# ZX_UNO_Aplus_HAT2.net
KiCad netlist of a schematic drawn in Altium Designer
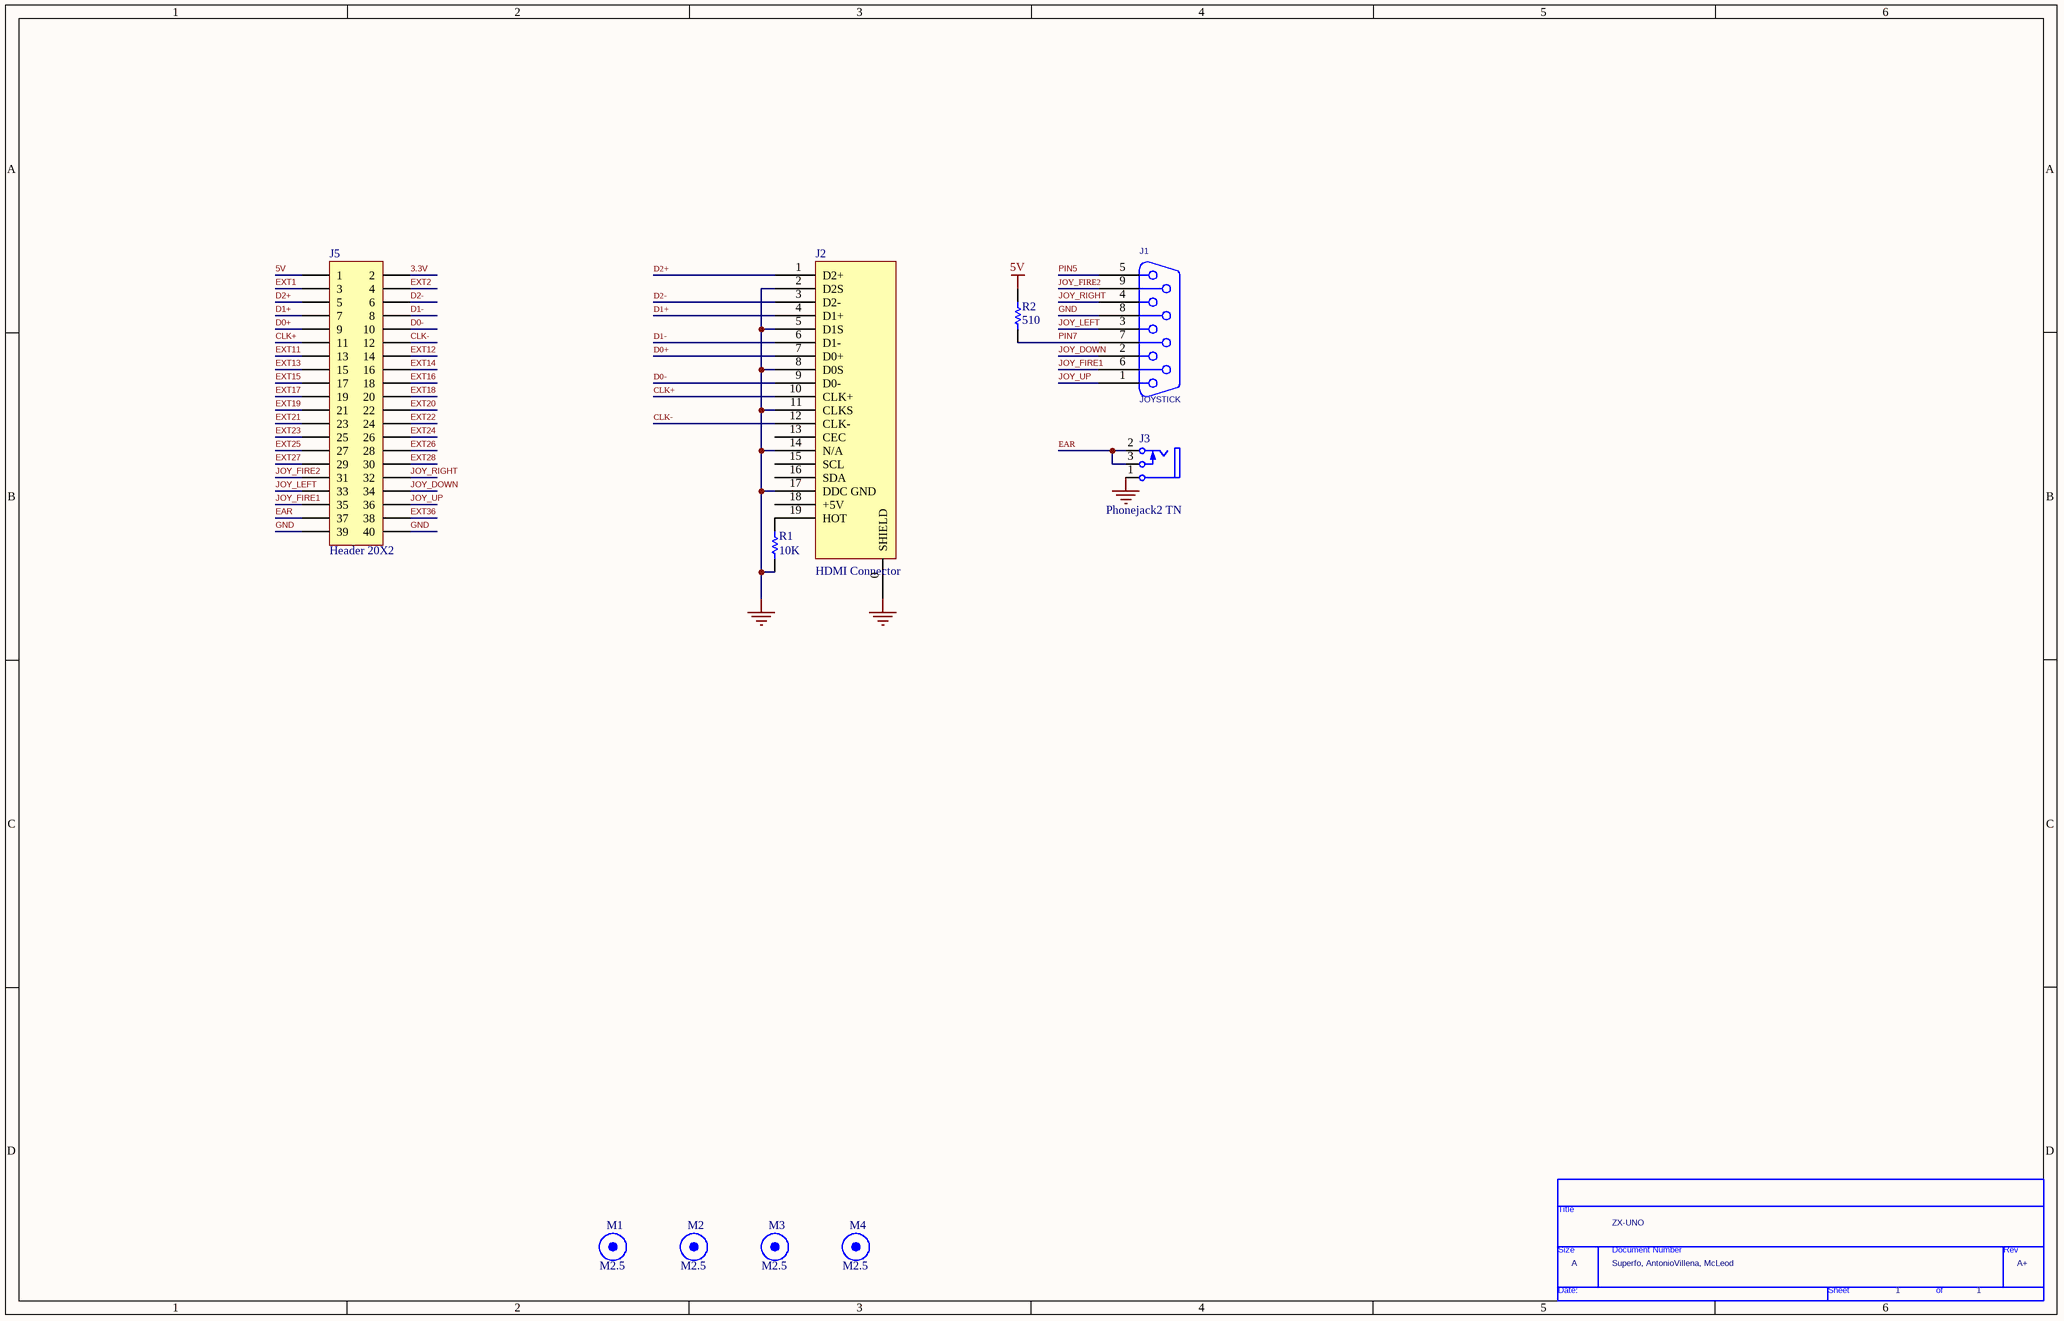
[diagram p0: ZX_UNO_Aplus_HAT2.SchDoc]

(export (version "E")
  (design (tool "Eeschema 10.0.6"))
  (components
    (comp (ref "*")
      (value "TitleBlock0")
      (fields
        (field (name "PAGE COUNT") "1")
        (field (name "PAGE NUMBER") "1")
        (field (name "PAGE SIZE") "A")
        (field (name "TITLE") "ZX-UNO")
        (field (name "REVCODE") "A+")
        (field (name "DOC") "Superfo, AntonioVillena, McLeod")
      )
      (libsource (lib "*") (part "TitleBlock0"))
    )
    (comp (ref "J1") (value "JOYSTICK") (libsource (lib "*") (part "CONNECTOR DB9")))
    (comp (ref "J2")
      (value "HDMI Connector")
      (footprint "HDMI 10029449")
      (description "HDMI, SMD, R/A KDMIX-NS1-WS-B")
      (libsource (lib "AltiumDesignLibrary") (part "HDMI-RA-Kycon"))
    )
    (comp (ref "J3")
      (value "Phonejack2 TN")
      (footprint "AUDIO  JACK MJ-3523-SMT")
      (description "Jack Socket, 3.5mm, Thru-Hole, Vertical, 2-Conductor with Tip closed")
      (fields (field (name "PUBLISHER") "Altium Limited"))
      (libsource (lib "Retro Computer") (part "Phonejack2 TN"))
    )
    (comp (ref "J5")
      (value "Header 20X2")
      (footprint "HDR2X20")
      (description "Header, 20-Pin, Dual row")
      (fields (field (name "PUBLISHER") "Altium Limited"))
      (libsource (lib "Miscellaneous Connectors") (part "Header 20X2"))
    )
    (comp (ref "M1") (value "M2.5") (footprint "M2.5") (libsource (lib "Misc Devices 2") (part "M2.5")))
    (comp (ref "M2") (value "M2.5") (footprint "M2.5") (libsource (lib "Misc Devices 2") (part "M2.5")))
    (comp (ref "M3") (value "M2.5") (footprint "M2.5") (libsource (lib "Misc Devices 2") (part "M2.5")))
    (comp (ref "M4") (value "M2.5") (footprint "M2.5") (libsource (lib "Misc Devices 2") (part "M2.5")))
    (comp (ref "R1")
      (value "10K")
      (footprint "SM/R_0805")
      (description "Resistor")
      (fields (field (name "Comment") "Res1") (field (name "PUBLISHER") "Altium Limited"))
      (libsource (lib "Miscellaneous Devices") (part "Res1"))
    )
    (comp (ref "R2")
      (value "510")
      (footprint "SM/R_0805")
      (description "Resistor")
      (fields (field (name "Comment") "Res1") (field (name "PUBLISHER") "Altium Limited"))
      (libsource (lib "Miscellaneous Devices") (part "Res1"))
    )
  )
  (nets
    (net (code "1") (name "/3.3V") (class "Default")
      (node (ref "J5") (pin "2") (pinfunction "2_2") (pintype "passive"))
    )
    (net (code "2") (name "/CLK+") (class "Default")
      (node (ref "J2") (pin "10") (pinfunction "CLK+_10") (pintype "passive"))
      (node (ref "J5") (pin "11") (pinfunction "11_11") (pintype "passive"))
    )
    (net (code "3") (name "/CLK-") (class "Default")
      (node (ref "J2") (pin "12") (pinfunction "CLK-_12") (pintype "passive"))
      (node (ref "J5") (pin "12") (pinfunction "12_12") (pintype "passive"))
    )
    (net (code "4") (name "/D0+") (class "Default")
      (node (ref "J2") (pin "7") (pinfunction "D0+_7") (pintype "passive"))
      (node (ref "J5") (pin "9") (pinfunction "9_9") (pintype "passive"))
    )
    (net (code "5") (name "/D0-") (class "Default")
      (node (ref "J2") (pin "9") (pinfunction "D0-_9") (pintype "passive"))
      (node (ref "J5") (pin "10") (pinfunction "10_10") (pintype "passive"))
    )
    (net (code "6") (name "/D1+") (class "Default")
      (node (ref "J2") (pin "4") (pinfunction "D1+_4") (pintype "passive"))
      (node (ref "J5") (pin "7") (pinfunction "7_7") (pintype "passive"))
    )
    (net (code "7") (name "/D1-") (class "Default")
      (node (ref "J2") (pin "6") (pinfunction "D1-_6") (pintype "passive"))
      (node (ref "J5") (pin "8") (pinfunction "8_8") (pintype "passive"))
    )
    (net (code "8") (name "/D2+") (class "Default")
      (node (ref "J2") (pin "1") (pinfunction "D2+_1") (pintype "passive"))
      (node (ref "J5") (pin "5") (pinfunction "5_5") (pintype "passive"))
    )
    (net (code "9") (name "/D2-") (class "Default")
      (node (ref "J2") (pin "3") (pinfunction "D2-_3") (pintype "passive"))
      (node (ref "J5") (pin "6") (pinfunction "6_6") (pintype "passive"))
    )
    (net (code "10") (name "/EAR") (class "Default")
      (node (ref "J3") (pin "2") (pinfunction "T_2") (pintype "passive"))
      (node (ref "J3") (pin "3") (pinfunction "TN_3") (pintype "passive"))
      (node (ref "J5") (pin "37") (pinfunction "37_37") (pintype "passive"))
    )
    (net (code "11") (name "/EXT1") (class "Default")
      (node (ref "J5") (pin "3") (pinfunction "3_3") (pintype "passive"))
    )
    (net (code "12") (name "/EXT2") (class "Default")
      (node (ref "J5") (pin "4") (pinfunction "4_4") (pintype "passive"))
    )
    (net (code "13") (name "/EXT11") (class "Default")
      (node (ref "J5") (pin "13") (pinfunction "13_13") (pintype "passive"))
    )
    (net (code "14") (name "/EXT12") (class "Default")
      (node (ref "J5") (pin "14") (pinfunction "14_14") (pintype "passive"))
    )
    (net (code "15") (name "/EXT13") (class "Default")
      (node (ref "J5") (pin "15") (pinfunction "15_15") (pintype "passive"))
    )
    (net (code "16") (name "/EXT14") (class "Default")
      (node (ref "J5") (pin "16") (pinfunction "16_16") (pintype "passive"))
    )
    (net (code "17") (name "/EXT15") (class "Default")
      (node (ref "J5") (pin "17") (pinfunction "17_17") (pintype "passive"))
    )
    (net (code "18") (name "/EXT16") (class "Default")
      (node (ref "J5") (pin "18") (pinfunction "18_18") (pintype "passive"))
    )
    (net (code "19") (name "/EXT17") (class "Default")
      (node (ref "J5") (pin "19") (pinfunction "19_19") (pintype "passive"))
    )
    (net (code "20") (name "/EXT18") (class "Default")
      (node (ref "J5") (pin "20") (pinfunction "20_20") (pintype "passive"))
    )
    (net (code "21") (name "/EXT19") (class "Default")
      (node (ref "J5") (pin "21") (pinfunction "21_21") (pintype "passive"))
    )
    (net (code "22") (name "/EXT20") (class "Default")
      (node (ref "J5") (pin "22") (pinfunction "22_22") (pintype "passive"))
    )
    (net (code "23") (name "/EXT21") (class "Default")
      (node (ref "J5") (pin "23") (pinfunction "23_23") (pintype "passive"))
    )
    (net (code "24") (name "/EXT22") (class "Default")
      (node (ref "J5") (pin "24") (pinfunction "24_24") (pintype "passive"))
    )
    (net (code "25") (name "/EXT23") (class "Default")
      (node (ref "J5") (pin "25") (pinfunction "25_25") (pintype "passive"))
    )
    (net (code "26") (name "/EXT24") (class "Default")
      (node (ref "J5") (pin "26") (pinfunction "26_26") (pintype "passive"))
    )
    (net (code "27") (name "/EXT25") (class "Default")
      (node (ref "J5") (pin "27") (pinfunction "27_27") (pintype "passive"))
    )
    (net (code "28") (name "/EXT26") (class "Default")
      (node (ref "J5") (pin "28") (pinfunction "28_28") (pintype "passive"))
    )
    (net (code "29") (name "/EXT27") (class "Default")
      (node (ref "J5") (pin "29") (pinfunction "29_29") (pintype "passive"))
    )
    (net (code "30") (name "/EXT28") (class "Default")
      (node (ref "J5") (pin "30") (pinfunction "30_30") (pintype "passive"))
    )
    (net (code "31") (name "/EXT36") (class "Default")
      (node (ref "J5") (pin "38") (pinfunction "38_38") (pintype "passive"))
    )
    (net (code "32") (name "/JOY_DOWN") (class "Default")
      (node (ref "J1") (pin "2") (pinfunction "2_2") (pintype "passive"))
      (node (ref "J5") (pin "34") (pinfunction "34_34") (pintype "passive"))
    )
    (net (code "33") (name "/JOY_FIRE1") (class "Default")
      (node (ref "J1") (pin "6") (pinfunction "6_6") (pintype "passive"))
      (node (ref "J5") (pin "35") (pinfunction "35_35") (pintype "passive"))
    )
    (net (code "34") (name "/JOY_FIRE2") (class "Default")
      (node (ref "J1") (pin "9") (pinfunction "9_9") (pintype "passive"))
      (node (ref "J5") (pin "31") (pinfunction "31_31") (pintype "passive"))
    )
    (net (code "35") (name "/JOY_LEFT") (class "Default")
      (node (ref "J1") (pin "3") (pinfunction "3_3") (pintype "passive"))
      (node (ref "J5") (pin "33") (pinfunction "33_33") (pintype "passive"))
    )
    (net (code "36") (name "/JOY_RIGHT") (class "Default")
      (node (ref "J1") (pin "4") (pinfunction "4_4") (pintype "passive"))
      (node (ref "J5") (pin "32") (pinfunction "32_32") (pintype "passive"))
    )
    (net (code "37") (name "/JOY_UP") (class "Default")
      (node (ref "J1") (pin "1") (pinfunction "1_1") (pintype "passive"))
      (node (ref "J5") (pin "36") (pinfunction "36_36") (pintype "passive"))
    )
    (net (code "38") (name "/PIN5") (class "Default")
      (node (ref "J1") (pin "5") (pinfunction "5_5") (pintype "passive"))
    )
    (net (code "39") (name "/PIN7") (class "Default")
      (node (ref "J1") (pin "7") (pinfunction "7_7") (pintype "passive"))
      (node (ref "R2") (pin "1") (pinfunction "1_1") (pintype "passive"))
    )
    (net (code "40") (name "5V") (class "Default")
      (node (ref "J5") (pin "1") (pinfunction "1_1") (pintype "passive"))
      (node (ref "R2") (pin "2") (pinfunction "2_2") (pintype "passive"))
    )
    (net (code "41") (name "GND") (class "Default")
      (node (ref "J1") (pin "8") (pinfunction "8_8") (pintype "passive"))
      (node (ref "J2") (pin "0") (pinfunction "SHIELD_0") (pintype "passive"))
      (node (ref "J2") (pin "11") (pinfunction "CLKS_11") (pintype "passive"))
      (node (ref "J2") (pin "14") (pinfunction "N/A_14") (pintype "passive"))
      (node (ref "J2") (pin "17") (pinfunction "DDC_GND_17") (pintype "passive"))
      (node (ref "J2") (pin "2") (pinfunction "D2S_2") (pintype "passive"))
      (node (ref "J2") (pin "5") (pinfunction "D1S_5") (pintype "passive"))
      (node (ref "J2") (pin "8") (pinfunction "D0S_8") (pintype "passive"))
      (node (ref "J3") (pin "1") (pinfunction "S_1") (pintype "power_in"))
      (node (ref "J5") (pin "39") (pinfunction "39_39") (pintype "passive"))
      (node (ref "J5") (pin "40") (pinfunction "40_40") (pintype "passive"))
      (node (ref "R1") (pin "1") (pinfunction "1_1") (pintype "passive"))
    )
    (net (code "42") (name "Net-(J2-HOT)") (class "Default")
      (node (ref "J2") (pin "19") (pinfunction "HOT_19") (pintype "passive"))
      (node (ref "R1") (pin "2") (pinfunction "2_2") (pintype "passive"))
    )
    (net (code "43") (name "unconnected-(J2-+5V-Pad18)") (class "Default")
      (node (ref "J2") (pin "18") (pinfunction "+5V_18") (pintype "passive"))
    )
    (net (code "44") (name "unconnected-(J2-CEC-Pad13)") (class "Default")
      (node (ref "J2") (pin "13") (pinfunction "CEC_13") (pintype "passive"))
    )
    (net (code "45") (name "unconnected-(J2-SCL-Pad15)") (class "Default")
      (node (ref "J2") (pin "15") (pinfunction "SCL_15") (pintype "passive"))
    )
    (net (code "46") (name "unconnected-(J2-SDA-Pad16)") (class "Default")
      (node (ref "J2") (pin "16") (pinfunction "SDA_16") (pintype "passive"))
    )
  )
)
